# Smart_LIghts.net
KiCad netlist of a schematic drawn in EAGLE
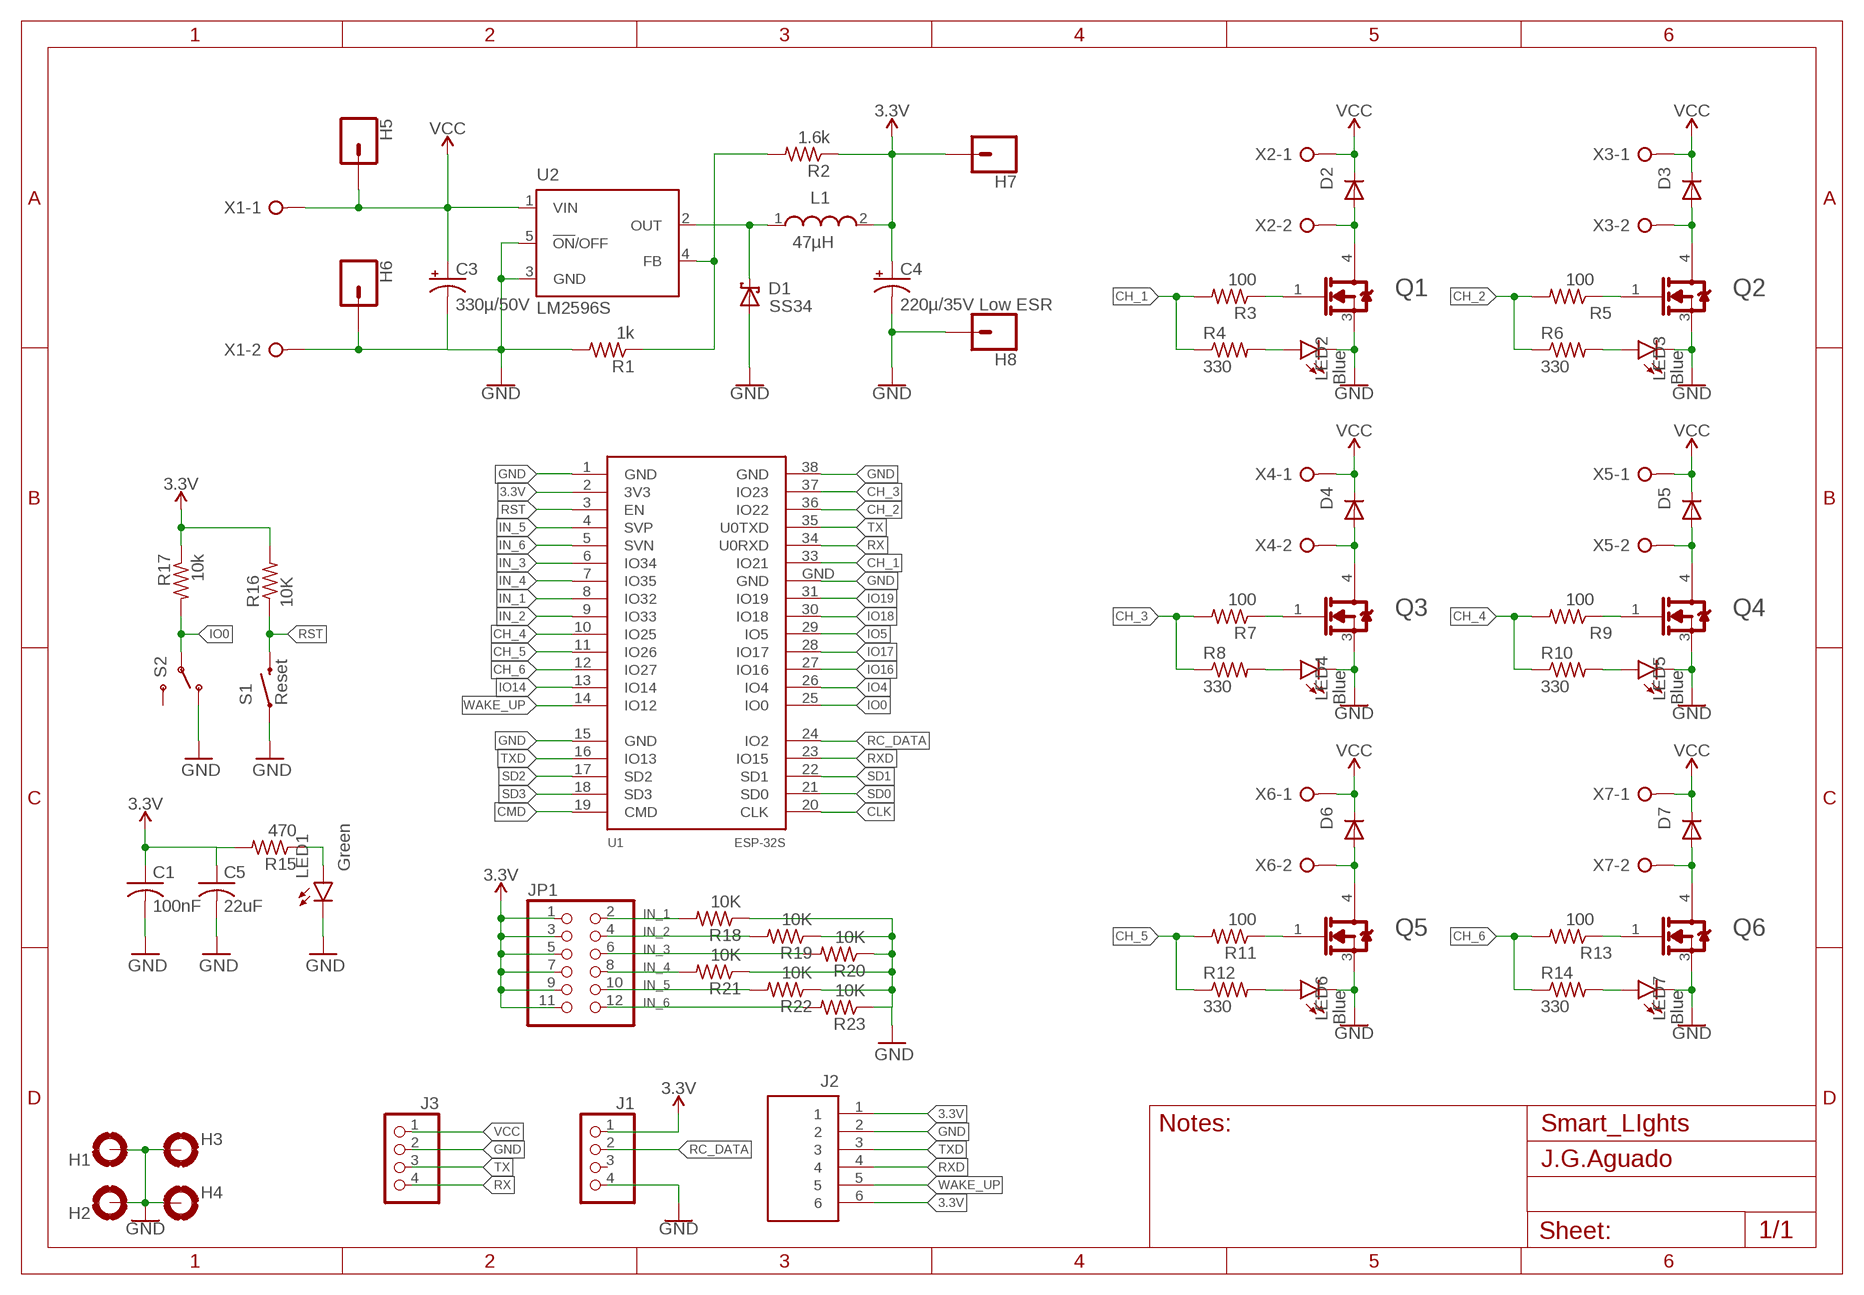
[diagram p0: schematic, sheet 1]

(export (version "E")
  (design (tool "Eeschema 10.0.6"))
  (components
    (comp (ref "C1")
      (value "100nF")
      (footprint "eagle-import:C0603")
      (libsource (lib "eagle-import") (part "C-USC0603"))
    )
    (comp (ref "C3")
      (value "330µ/50V")
      (footprint "eagle-import:PANASONIC_F")
      (fields (field (name "MF") "Panasonic"))
      (libsource (lib "eagle-import") (part "CPOL-USF"))
    )
    (comp (ref "C4")
      (value "220µ/35V Low ESR")
      (footprint "eagle-import:PANASONIC_F")
      (fields (field (name "MF") "Panasonic"))
      (libsource (lib "eagle-import") (part "CPOL-USF"))
    )
    (comp (ref "C5")
      (value "22uF")
      (footprint "eagle-import:C0603")
      (libsource (lib "eagle-import") (part "C-USC0603"))
    )
    (comp (ref "D1")
      (value "SS34")
      (footprint "eagle-import:SMB")
      (libsource (lib "eagle-import") (part "SCHOTTKY-DIODESMD"))
    )
    (comp (ref "D2")
      (value "DIODE-SOD123")
      (footprint "eagle-import:SOD123")
      (libsource (lib "eagle-import") (part "DIODE-SOD123"))
    )
    (comp (ref "D3")
      (value "DIODE-SOD123")
      (footprint "eagle-import:SOD123")
      (libsource (lib "eagle-import") (part "DIODE-SOD123"))
    )
    (comp (ref "D4")
      (value "DIODE-SOD123")
      (footprint "eagle-import:SOD123")
      (libsource (lib "eagle-import") (part "DIODE-SOD123"))
    )
    (comp (ref "D5")
      (value "DIODE-SOD123")
      (footprint "eagle-import:SOD123")
      (libsource (lib "eagle-import") (part "DIODE-SOD123"))
    )
    (comp (ref "D6")
      (value "DIODE-SOD123")
      (footprint "eagle-import:SOD123")
      (libsource (lib "eagle-import") (part "DIODE-SOD123"))
    )
    (comp (ref "D7")
      (value "DIODE-SOD123")
      (footprint "eagle-import:SOD123")
      (libsource (lib "eagle-import") (part "DIODE-SOD123"))
    )
    (comp (ref "H1")
      (value "MOUNT-PAD-ROUND3.0")
      (footprint "eagle-import:3,0-PAD")
      (libsource (lib "eagle-import") (part "MOUNT-PAD-ROUND3.0"))
    )
    (comp (ref "H2")
      (value "MOUNT-PAD-ROUND3.0")
      (footprint "eagle-import:3,0-PAD")
      (libsource (lib "eagle-import") (part "MOUNT-PAD-ROUND3.0"))
    )
    (comp (ref "H3")
      (value "MOUNT-PAD-ROUND3.0")
      (footprint "eagle-import:3,0-PAD")
      (libsource (lib "eagle-import") (part "MOUNT-PAD-ROUND3.0"))
    )
    (comp (ref "H4")
      (value "MOUNT-PAD-ROUND3.0")
      (footprint "eagle-import:3,0-PAD")
      (libsource (lib "eagle-import") (part "MOUNT-PAD-ROUND3.0"))
    )
    (comp (ref "H5")
      (value "CONN_01PTH_2MM")
      (footprint "eagle-import:1X01_2MM")
      (libsource (lib "eagle-import") (part "CONN_01PTH_2MM"))
    )
    (comp (ref "H6")
      (value "CONN_01PTH_2MM")
      (footprint "eagle-import:1X01_2MM")
      (libsource (lib "eagle-import") (part "CONN_01PTH_2MM"))
    )
    (comp (ref "H7")
      (value "CONN_01PTH_2MM")
      (footprint "eagle-import:1X01_2MM")
      (libsource (lib "eagle-import") (part "CONN_01PTH_2MM"))
    )
    (comp (ref "H8")
      (value "CONN_01PTH_2MM")
      (footprint "eagle-import:1X01_2MM")
      (libsource (lib "eagle-import") (part "CONN_01PTH_2MM"))
    )
    (comp (ref "J1")
      (value "PINHD-1X4")
      (footprint "eagle-import:1X04")
      (libsource (lib "eagle-import") (part "PINHD-1X4"))
    )
    (comp (ref "J2")
      (value "JST_6_PIN_VERTICAL")
      (footprint "eagle-import:JST-6-SMD-VERT-1.0MM")
      (libsource (lib "eagle-import") (part "JST_6_PIN_VERTICAL"))
    )
    (comp (ref "J3")
      (value "PINHD-1X4")
      (footprint "eagle-import:1X04")
      (libsource (lib "eagle-import") (part "PINHD-1X4"))
    )
    (comp (ref "JP1")
      (value "PINHD-2X6")
      (footprint "eagle-import:2X06")
      (libsource (lib "eagle-import") (part "PINHD-2X6"))
    )
    (comp (ref "L1")
      (value "47µH")
      (footprint "eagle-import:WE-PD_1260_1245_1280_1210")
      (fields (field (name "MF") "Wuerth"))
      (libsource (lib "eagle-import") (part "WE-PD_1260/1245/1280/1210"))
    )
    (comp (ref "LED1")
      (value "Green")
      (footprint "eagle-import:SML0603")
      (libsource (lib "eagle-import") (part "LEDSML0603"))
    )
    (comp (ref "LED2")
      (value "Blue")
      (footprint "eagle-import:SML0603")
      (libsource (lib "eagle-import") (part "LEDSML0603"))
    )
    (comp (ref "LED3")
      (value "Blue")
      (footprint "eagle-import:SML0603")
      (libsource (lib "eagle-import") (part "LEDSML0603"))
    )
    (comp (ref "LED4")
      (value "Blue")
      (footprint "eagle-import:SML0603")
      (libsource (lib "eagle-import") (part "LEDSML0603"))
    )
    (comp (ref "LED5")
      (value "Blue")
      (footprint "eagle-import:SML0603")
      (libsource (lib "eagle-import") (part "LEDSML0603"))
    )
    (comp (ref "LED6")
      (value "Blue")
      (footprint "eagle-import:SML0603")
      (libsource (lib "eagle-import") (part "LEDSML0603"))
    )
    (comp (ref "LED7")
      (value "Blue")
      (footprint "eagle-import:SML0603")
      (libsource (lib "eagle-import") (part "LEDSML0603"))
    )
    (comp (ref "Q1")
      (value "IRLR2905TRPBF")
      (footprint "eagle-import:INFINEON_TECHNOLOGIES_IRLR2905TRPBF_0")
      (fields
        (field (name "DIGIKEY_PART_NUMBER") "IRLR2905PBFCT-ND")
        (field (name "MF") "Infineon Technologies")
        (field (name "MOUSER_PART_NUMBER") "942-IRLR2905TRPBF")
      )
      (libsource (lib "eagle-import") (part "INFINEON_TECHNOLOGIES_IRLR2905TRPBFINFINEON_TECHNOLOGIES_IRLR2905TRPBF_0_0"))
    )
    (comp (ref "Q2")
      (value "IRLR2905TRPBF")
      (footprint "eagle-import:INFINEON_TECHNOLOGIES_IRLR2905TRPBF_0")
      (fields
        (field (name "DIGIKEY_PART_NUMBER") "IRLR2905PBFCT-ND")
        (field (name "MF") "Infineon Technologies")
        (field (name "MOUSER_PART_NUMBER") "942-IRLR2905TRPBF")
      )
      (libsource (lib "eagle-import") (part "INFINEON_TECHNOLOGIES_IRLR2905TRPBFINFINEON_TECHNOLOGIES_IRLR2905TRPBF_0_0"))
    )
    (comp (ref "Q3")
      (value "IRLR2905TRPBF")
      (footprint "eagle-import:INFINEON_TECHNOLOGIES_IRLR2905TRPBF_0")
      (fields
        (field (name "DIGIKEY_PART_NUMBER") "IRLR2905PBFCT-ND")
        (field (name "MF") "Infineon Technologies")
        (field (name "MOUSER_PART_NUMBER") "942-IRLR2905TRPBF")
      )
      (libsource (lib "eagle-import") (part "INFINEON_TECHNOLOGIES_IRLR2905TRPBFINFINEON_TECHNOLOGIES_IRLR2905TRPBF_0_0"))
    )
    (comp (ref "Q4")
      (value "IRLR2905TRPBF")
      (footprint "eagle-import:INFINEON_TECHNOLOGIES_IRLR2905TRPBF_0")
      (fields
        (field (name "DIGIKEY_PART_NUMBER") "IRLR2905PBFCT-ND")
        (field (name "MF") "Infineon Technologies")
        (field (name "MOUSER_PART_NUMBER") "942-IRLR2905TRPBF")
      )
      (libsource (lib "eagle-import") (part "INFINEON_TECHNOLOGIES_IRLR2905TRPBFINFINEON_TECHNOLOGIES_IRLR2905TRPBF_0_0"))
    )
    (comp (ref "Q5")
      (value "IRLR2905TRPBF")
      (footprint "eagle-import:INFINEON_TECHNOLOGIES_IRLR2905TRPBF_0")
      (fields
        (field (name "DIGIKEY_PART_NUMBER") "IRLR2905PBFCT-ND")
        (field (name "MF") "Infineon Technologies")
        (field (name "MOUSER_PART_NUMBER") "942-IRLR2905TRPBF")
      )
      (libsource (lib "eagle-import") (part "INFINEON_TECHNOLOGIES_IRLR2905TRPBFINFINEON_TECHNOLOGIES_IRLR2905TRPBF_0_0"))
    )
    (comp (ref "Q6")
      (value "IRLR2905TRPBF")
      (footprint "eagle-import:INFINEON_TECHNOLOGIES_IRLR2905TRPBF_0")
      (fields
        (field (name "DIGIKEY_PART_NUMBER") "IRLR2905PBFCT-ND")
        (field (name "MF") "Infineon Technologies")
        (field (name "MOUSER_PART_NUMBER") "942-IRLR2905TRPBF")
      )
      (libsource (lib "eagle-import") (part "INFINEON_TECHNOLOGIES_IRLR2905TRPBFINFINEON_TECHNOLOGIES_IRLR2905TRPBF_0_0"))
    )
    (comp (ref "R1")
      (value "1k")
      (footprint "eagle-import:R0603")
      (libsource (lib "eagle-import") (part "R-US_R0603"))
    )
    (comp (ref "R2")
      (value "1.6k")
      (footprint "eagle-import:R0603")
      (libsource (lib "eagle-import") (part "R-US_R0603"))
    )
    (comp (ref "R3")
      (value "100")
      (footprint "eagle-import:R0603")
      (libsource (lib "eagle-import") (part "R-US_R0603"))
    )
    (comp (ref "R4")
      (value "330")
      (footprint "eagle-import:R0603")
      (libsource (lib "eagle-import") (part "R-US_R0603"))
    )
    (comp (ref "R5")
      (value "100")
      (footprint "eagle-import:R0603")
      (libsource (lib "eagle-import") (part "R-US_R0603"))
    )
    (comp (ref "R6")
      (value "330")
      (footprint "eagle-import:R0603")
      (libsource (lib "eagle-import") (part "R-US_R0603"))
    )
    (comp (ref "R7")
      (value "100")
      (footprint "eagle-import:R0603")
      (libsource (lib "eagle-import") (part "R-US_R0603"))
    )
    (comp (ref "R8")
      (value "330")
      (footprint "eagle-import:R0603")
      (libsource (lib "eagle-import") (part "R-US_R0603"))
    )
    (comp (ref "R9")
      (value "100")
      (footprint "eagle-import:R0603")
      (libsource (lib "eagle-import") (part "R-US_R0603"))
    )
    (comp (ref "R10")
      (value "330")
      (footprint "eagle-import:R0603")
      (libsource (lib "eagle-import") (part "R-US_R0603"))
    )
    (comp (ref "R11")
      (value "100")
      (footprint "eagle-import:R0603")
      (libsource (lib "eagle-import") (part "R-US_R0603"))
    )
    (comp (ref "R12")
      (value "330")
      (footprint "eagle-import:R0603")
      (libsource (lib "eagle-import") (part "R-US_R0603"))
    )
    (comp (ref "R13")
      (value "100")
      (footprint "eagle-import:R0603")
      (libsource (lib "eagle-import") (part "R-US_R0603"))
    )
    (comp (ref "R14")
      (value "330")
      (footprint "eagle-import:R0603")
      (libsource (lib "eagle-import") (part "R-US_R0603"))
    )
    (comp (ref "R15")
      (value "470")
      (footprint "eagle-import:R0603")
      (libsource (lib "eagle-import") (part "R-US_R0603"))
    )
    (comp (ref "R16")
      (value "10K")
      (footprint "eagle-import:R0603")
      (libsource (lib "eagle-import") (part "R-US_R0603"))
    )
    (comp (ref "R17")
      (value "10k")
      (footprint "eagle-import:R0603")
      (libsource (lib "eagle-import") (part "R-US_R0603"))
    )
    (comp (ref "R18")
      (value "10K")
      (footprint "eagle-import:R0603")
      (libsource (lib "eagle-import") (part "R-US_R0603"))
    )
    (comp (ref "R19")
      (value "10K")
      (footprint "eagle-import:R0603")
      (libsource (lib "eagle-import") (part "R-US_R0603"))
    )
    (comp (ref "R20")
      (value "10K")
      (footprint "eagle-import:R0603")
      (libsource (lib "eagle-import") (part "R-US_R0603"))
    )
    (comp (ref "R21")
      (value "10K")
      (footprint "eagle-import:R0603")
      (libsource (lib "eagle-import") (part "R-US_R0603"))
    )
    (comp (ref "R22")
      (value "10K")
      (footprint "eagle-import:R0603")
      (libsource (lib "eagle-import") (part "R-US_R0603"))
    )
    (comp (ref "R23")
      (value "10K")
      (footprint "eagle-import:R0603")
      (libsource (lib "eagle-import") (part "R-US_R0603"))
    )
    (comp (ref "S1")
      (value "Reset")
      (footprint "eagle-import:TACTILE_SWITCH_TALL")
      (libsource (lib "eagle-import") (part "SWITCH-MOMENTARY-2SMD-4"))
    )
    (comp (ref "S2")
      (value "SWITCH_SPDT")
      (footprint "eagle-import:KPS-1290")
      (libsource (lib "eagle-import") (part "SWITCH_SPDT"))
    )
    (comp (ref "U1")
      (value "ESP-32S")
      (footprint "eagle-import:ESP-32S")
      (libsource (lib "eagle-import") (part "ESP-32S"))
    )
    (comp (ref "U2")
      (value "LM2596S")
      (footprint "eagle-import:TO263-5")
      (fields (field (name "MF") "NATIONAL SEMICONDUCTOR") (field (name "MPN") "LM2596S-ADJ/NOPB"))
      (libsource (lib "eagle-import") (part "LM2596S"))
    )
    (comp (ref "X1")
      (value "W237-02P")
      (footprint "eagle-import:W237-132")
      (libsource (lib "eagle-import") (part "W237-02P"))
    )
    (comp (ref "X2")
      (value "W237-02P")
      (footprint "eagle-import:W237-132")
      (libsource (lib "eagle-import") (part "W237-02P"))
    )
    (comp (ref "X3")
      (value "W237-02P")
      (footprint "eagle-import:W237-132")
      (libsource (lib "eagle-import") (part "W237-02P"))
    )
    (comp (ref "X4")
      (value "W237-02P")
      (footprint "eagle-import:W237-132")
      (libsource (lib "eagle-import") (part "W237-02P"))
    )
    (comp (ref "X5")
      (value "W237-02P")
      (footprint "eagle-import:W237-132")
      (libsource (lib "eagle-import") (part "W237-02P"))
    )
    (comp (ref "X6")
      (value "W237-02P")
      (footprint "eagle-import:W237-132")
      (libsource (lib "eagle-import") (part "W237-02P"))
    )
    (comp (ref "X7")
      (value "W237-02P")
      (footprint "eagle-import:W237-132")
      (libsource (lib "eagle-import") (part "W237-02P"))
    )
  )
  (nets
    (net (code "1") (name "3.3V") (class "Default")
      (node (ref "C1") (pin "1") (pinfunction "1_1") (pintype "passive"))
      (node (ref "C4") (pin "+") (pinfunction "+_+") (pintype "passive"))
      (node (ref "C5") (pin "1") (pinfunction "1_1") (pintype "passive"))
      (node (ref "H7") (pin "1") (pinfunction "1_1") (pintype "passive"))
      (node (ref "J1") (pin "1") (pinfunction "1_1") (pintype "passive"))
      (node (ref "J2") (pin "1") (pinfunction "1_1") (pintype "bidirectional"))
      (node (ref "J2") (pin "6") (pinfunction "6_6") (pintype "bidirectional"))
      (node (ref "JP1") (pin "1") (pinfunction "1_1") (pintype "passive"))
      (node (ref "JP1") (pin "11") (pinfunction "11_11") (pintype "passive"))
      (node (ref "JP1") (pin "3") (pinfunction "3_3") (pintype "passive"))
      (node (ref "JP1") (pin "5") (pinfunction "5_5") (pintype "passive"))
      (node (ref "JP1") (pin "7") (pinfunction "7_7") (pintype "passive"))
      (node (ref "JP1") (pin "9") (pinfunction "9_9") (pintype "passive"))
      (node (ref "L1") (pin "2") (pinfunction "2_2") (pintype "passive"))
      (node (ref "R15") (pin "2") (pinfunction "2_2") (pintype "passive"))
      (node (ref "R16") (pin "2") (pinfunction "2_2") (pintype "passive"))
      (node (ref "R17") (pin "1") (pinfunction "1_1") (pintype "passive"))
      (node (ref "R2") (pin "1") (pinfunction "1_1") (pintype "passive"))
      (node (ref "U1") (pin "2") (pinfunction "3V3_2") (pintype "power_in"))
    )
    (net (code "2") (name "CH_1") (class "Default")
      (node (ref "R3") (pin "2") (pinfunction "2_2") (pintype "passive"))
      (node (ref "R4") (pin "1") (pinfunction "1_1") (pintype "passive"))
      (node (ref "U1") (pin "33") (pinfunction "IO21_33") (pintype "bidirectional"))
    )
    (net (code "3") (name "CH_2") (class "Default")
      (node (ref "R5") (pin "2") (pinfunction "2_2") (pintype "passive"))
      (node (ref "R6") (pin "1") (pinfunction "1_1") (pintype "passive"))
      (node (ref "U1") (pin "36") (pinfunction "IO22_36") (pintype "bidirectional"))
    )
    (net (code "4") (name "CH_3") (class "Default")
      (node (ref "R7") (pin "2") (pinfunction "2_2") (pintype "passive"))
      (node (ref "R8") (pin "1") (pinfunction "1_1") (pintype "passive"))
      (node (ref "U1") (pin "37") (pinfunction "IO23_37") (pintype "bidirectional"))
    )
    (net (code "5") (name "CH_4") (class "Default")
      (node (ref "R10") (pin "1") (pinfunction "1_1") (pintype "passive"))
      (node (ref "R9") (pin "2") (pinfunction "2_2") (pintype "passive"))
      (node (ref "U1") (pin "10") (pinfunction "IO25_10") (pintype "bidirectional"))
    )
    (net (code "6") (name "CH_5") (class "Default")
      (node (ref "R11") (pin "2") (pinfunction "2_2") (pintype "passive"))
      (node (ref "R12") (pin "1") (pinfunction "1_1") (pintype "passive"))
      (node (ref "U1") (pin "11") (pinfunction "IO26_11") (pintype "bidirectional"))
    )
    (net (code "7") (name "CH_6") (class "Default")
      (node (ref "R13") (pin "2") (pinfunction "2_2") (pintype "passive"))
      (node (ref "R14") (pin "1") (pinfunction "1_1") (pintype "passive"))
      (node (ref "U1") (pin "12") (pinfunction "IO27_12") (pintype "bidirectional"))
    )
    (net (code "8") (name "CLK") (class "Default")
      (node (ref "U1") (pin "20") (pinfunction "CLK_20") (pintype "bidirectional"))
    )
    (net (code "9") (name "CMD") (class "Default")
      (node (ref "U1") (pin "19") (pinfunction "CMD_19") (pintype "bidirectional"))
    )
    (net (code "10") (name "GND") (class "Default")
      (node (ref "C1") (pin "2") (pinfunction "2_2") (pintype "passive"))
      (node (ref "C3") (pin "-") (pinfunction "-_-") (pintype "passive"))
      (node (ref "C4") (pin "-") (pinfunction "-_-") (pintype "passive"))
      (node (ref "C5") (pin "2") (pinfunction "2_2") (pintype "passive"))
      (node (ref "D1") (pin "A") (pinfunction "A_A") (pintype "passive"))
      (node (ref "H1") (pin "B3,0") (pinfunction "MOUNT_B3,0") (pintype "passive"))
      (node (ref "H2") (pin "B3,0") (pinfunction "MOUNT_B3,0") (pintype "passive"))
      (node (ref "H3") (pin "B3,0") (pinfunction "MOUNT_B3,0") (pintype "passive"))
      (node (ref "H4") (pin "B3,0") (pinfunction "MOUNT_B3,0") (pintype "passive"))
      (node (ref "H6") (pin "1") (pinfunction "1_1") (pintype "passive"))
      (node (ref "H8") (pin "1") (pinfunction "1_1") (pintype "passive"))
      (node (ref "J1") (pin "4") (pinfunction "4_4") (pintype "passive"))
      (node (ref "J2") (pin "2") (pinfunction "2_2") (pintype "bidirectional"))
      (node (ref "J3") (pin "2") (pinfunction "2_2") (pintype "passive"))
      (node (ref "LED1") (pin "C") (pinfunction "C_C") (pintype "passive"))
      (node (ref "LED2") (pin "C") (pinfunction "C_C") (pintype "passive"))
      (node (ref "LED3") (pin "C") (pinfunction "C_C") (pintype "passive"))
      (node (ref "LED4") (pin "C") (pinfunction "C_C") (pintype "passive"))
      (node (ref "LED5") (pin "C") (pinfunction "C_C") (pintype "passive"))
      (node (ref "LED6") (pin "C") (pinfunction "C_C") (pintype "passive"))
      (node (ref "LED7") (pin "C") (pinfunction "C_C") (pintype "passive"))
      (node (ref "Q1") (pin "3") (pinfunction "SOURCE_3") (pintype "passive"))
      (node (ref "Q2") (pin "3") (pinfunction "SOURCE_3") (pintype "passive"))
      (node (ref "Q3") (pin "3") (pinfunction "SOURCE_3") (pintype "passive"))
      (node (ref "Q4") (pin "3") (pinfunction "SOURCE_3") (pintype "passive"))
      (node (ref "Q5") (pin "3") (pinfunction "SOURCE_3") (pintype "passive"))
      (node (ref "Q6") (pin "3") (pinfunction "SOURCE_3") (pintype "passive"))
      (node (ref "R1") (pin "2") (pinfunction "2_2") (pintype "passive"))
      (node (ref "R18") (pin "1") (pinfunction "1_1") (pintype "passive"))
      (node (ref "R19") (pin "1") (pinfunction "1_1") (pintype "passive"))
      (node (ref "R20") (pin "1") (pinfunction "1_1") (pintype "passive"))
      (node (ref "R21") (pin "1") (pinfunction "1_1") (pintype "passive"))
      (node (ref "R22") (pin "1") (pinfunction "1_1") (pintype "passive"))
      (node (ref "R23") (pin "1") (pinfunction "1_1") (pintype "passive"))
      (node (ref "S1") (pin "A2") (pinfunction "1_A2") (pintype "passive"))
      (node (ref "S2") (pin "O") (pinfunction "O_O") (pintype "passive"))
      (node (ref "U1") (pin "1") (pinfunction "GND_1") (pintype "power_in"))
      (node (ref "U1") (pin "15") (pinfunction "GND_15") (pintype "power_in"))
      (node (ref "U1") (pin "38") (pinfunction "GND_38") (pintype "power_in"))
      (node (ref "U1") (pin "GND") (pinfunction "GND_GND") (pintype "power_in"))
      (node (ref "U2") (pin "3") (pinfunction "GND_3") (pintype "power_in"))
      (node (ref "U2") (pin "5") (pinfunction "~{ON}/OFF_5") (pintype "input"))
      (node (ref "X1") (pin "2") (pinfunction "KL_2") (pintype "passive"))
    )
    (net (code "11") (name "IN_1") (class "Default")
      (node (ref "JP1") (pin "2") (pinfunction "2_2") (pintype "passive"))
      (node (ref "R18") (pin "2") (pinfunction "2_2") (pintype "passive"))
      (node (ref "U1") (pin "8") (pinfunction "IO32_8") (pintype "bidirectional"))
    )
    (net (code "12") (name "IN_2") (class "Default")
      (node (ref "JP1") (pin "4") (pinfunction "4_4") (pintype "passive"))
      (node (ref "R19") (pin "2") (pinfunction "2_2") (pintype "passive"))
      (node (ref "U1") (pin "9") (pinfunction "IO33_9") (pintype "bidirectional"))
    )
    (net (code "13") (name "IN_3") (class "Default")
      (node (ref "JP1") (pin "6") (pinfunction "6_6") (pintype "passive"))
      (node (ref "R20") (pin "2") (pinfunction "2_2") (pintype "passive"))
      (node (ref "U1") (pin "6") (pinfunction "IO34_6") (pintype "bidirectional"))
    )
    (net (code "14") (name "IN_4") (class "Default")
      (node (ref "JP1") (pin "8") (pinfunction "8_8") (pintype "passive"))
      (node (ref "R21") (pin "2") (pinfunction "2_2") (pintype "passive"))
      (node (ref "U1") (pin "7") (pinfunction "IO35_7") (pintype "bidirectional"))
    )
    (net (code "15") (name "IN_5") (class "Default")
      (node (ref "JP1") (pin "10") (pinfunction "10_10") (pintype "passive"))
      (node (ref "R22") (pin "2") (pinfunction "2_2") (pintype "passive"))
      (node (ref "U1") (pin "4") (pinfunction "SVP_4") (pintype "bidirectional"))
    )
    (net (code "16") (name "IN_6") (class "Default")
      (node (ref "JP1") (pin "12") (pinfunction "12_12") (pintype "passive"))
      (node (ref "R23") (pin "2") (pinfunction "2_2") (pintype "passive"))
      (node (ref "U1") (pin "5") (pinfunction "SVN_5") (pintype "bidirectional"))
    )
    (net (code "17") (name "IO0") (class "Default")
      (node (ref "R17") (pin "2") (pinfunction "2_2") (pintype "passive"))
      (node (ref "S2") (pin "P") (pinfunction "P_P") (pintype "passive"))
      (node (ref "U1") (pin "25") (pinfunction "IO0_25") (pintype "bidirectional"))
    )
    (net (code "18") (name "IO4") (class "Default")
      (node (ref "U1") (pin "26") (pinfunction "IO4_26") (pintype "bidirectional"))
    )
    (net (code "19") (name "IO5") (class "Default")
      (node (ref "U1") (pin "29") (pinfunction "IO5_29") (pintype "bidirectional"))
    )
    (net (code "20") (name "IO14") (class "Default")
      (node (ref "U1") (pin "13") (pinfunction "IO14_13") (pintype "bidirectional"))
    )
    (net (code "21") (name "IO16") (class "Default")
      (node (ref "U1") (pin "27") (pinfunction "IO16_27") (pintype "bidirectional"))
    )
    (net (code "22") (name "IO17") (class "Default")
      (node (ref "U1") (pin "28") (pinfunction "IO17_28") (pintype "bidirectional"))
    )
    (net (code "23") (name "IO18") (class "Default")
      (node (ref "U1") (pin "30") (pinfunction "IO18_30") (pintype "bidirectional"))
    )
    (net (code "24") (name "IO19") (class "Default")
      (node (ref "U1") (pin "31") (pinfunction "IO19_31") (pintype "bidirectional"))
    )
    (net (code "25") (name "Net-(LED1-PadA)") (class "Default")
      (node (ref "LED1") (pin "A") (pinfunction "A_A") (pintype "passive"))
      (node (ref "R15") (pin "1") (pinfunction "1_1") (pintype "passive"))
    )
    (net (code "26") (name "Net-(LED2-PadA)") (class "Default")
      (node (ref "LED2") (pin "A") (pinfunction "A_A") (pintype "passive"))
      (node (ref "R4") (pin "2") (pinfunction "2_2") (pintype "passive"))
    )
    (net (code "27") (name "Net-(LED3-PadA)") (class "Default")
      (node (ref "LED3") (pin "A") (pinfunction "A_A") (pintype "passive"))
      (node (ref "R6") (pin "2") (pinfunction "2_2") (pintype "passive"))
    )
    (net (code "28") (name "Net-(LED4-PadA)") (class "Default")
      (node (ref "LED4") (pin "A") (pinfunction "A_A") (pintype "passive"))
      (node (ref "R8") (pin "2") (pinfunction "2_2") (pintype "passive"))
    )
    (net (code "29") (name "Net-(LED5-PadA)") (class "Default")
      (node (ref "LED5") (pin "A") (pinfunction "A_A") (pintype "passive"))
      (node (ref "R10") (pin "2") (pinfunction "2_2") (pintype "passive"))
    )
    (net (code "30") (name "Net-(LED6-PadA)") (class "Default")
      (node (ref "LED6") (pin "A") (pinfunction "A_A") (pintype "passive"))
      (node (ref "R12") (pin "2") (pinfunction "2_2") (pintype "passive"))
    )
    (net (code "31") (name "Net-(LED7-PadA)") (class "Default")
      (node (ref "LED7") (pin "A") (pinfunction "A_A") (pintype "passive"))
      (node (ref "R14") (pin "2") (pinfunction "2_2") (pintype "passive"))
    )
    (net (code "32") (name "Net-(Q1-DRAIN)") (class "Default")
      (node (ref "D2") (pin "A") (pinfunction "A_A") (pintype "passive"))
      (node (ref "Q1") (pin "4") (pinfunction "DRAIN_4") (pintype "passive"))
      (node (ref "X2") (pin "2") (pinfunction "KL_2") (pintype "passive"))
    )
    (net (code "33") (name "Net-(Q1-GATE)") (class "Default")
      (node (ref "Q1") (pin "1") (pinfunction "GATE_1") (pintype "passive"))
      (node (ref "R3") (pin "1") (pinfunction "1_1") (pintype "passive"))
    )
    (net (code "34") (name "Net-(Q2-DRAIN)") (class "Default")
      (node (ref "D3") (pin "A") (pinfunction "A_A") (pintype "passive"))
      (node (ref "Q2") (pin "4") (pinfunction "DRAIN_4") (pintype "passive"))
      (node (ref "X3") (pin "2") (pinfunction "KL_2") (pintype "passive"))
    )
    (net (code "35") (name "Net-(Q2-GATE)") (class "Default")
      (node (ref "Q2") (pin "1") (pinfunction "GATE_1") (pintype "passive"))
      (node (ref "R5") (pin "1") (pinfunction "1_1") (pintype "passive"))
    )
    (net (code "36") (name "Net-(Q3-DRAIN)") (class "Default")
      (node (ref "D4") (pin "A") (pinfunction "A_A") (pintype "passive"))
      (node (ref "Q3") (pin "4") (pinfunction "DRAIN_4") (pintype "passive"))
      (node (ref "X4") (pin "2") (pinfunction "KL_2") (pintype "passive"))
    )
    (net (code "37") (name "Net-(Q3-GATE)") (class "Default")
      (node (ref "Q3") (pin "1") (pinfunction "GATE_1") (pintype "passive"))
      (node (ref "R7") (pin "1") (pinfunction "1_1") (pintype "passive"))
    )
    (net (code "38") (name "Net-(Q4-DRAIN)") (class "Default")
      (node (ref "D5") (pin "A") (pinfunction "A_A") (pintype "passive"))
      (node (ref "Q4") (pin "4") (pinfunction "DRAIN_4") (pintype "passive"))
      (node (ref "X5") (pin "2") (pinfunction "KL_2") (pintype "passive"))
    )
    (net (code "39") (name "Net-(Q4-GATE)") (class "Default")
      (node (ref "Q4") (pin "1") (pinfunction "GATE_1") (pintype "passive"))
      (node (ref "R9") (pin "1") (pinfunction "1_1") (pintype "passive"))
    )
    (net (code "40") (name "Net-(Q5-DRAIN)") (class "Default")
      (node (ref "D6") (pin "A") (pinfunction "A_A") (pintype "passive"))
      (node (ref "Q5") (pin "4") (pinfunction "DRAIN_4") (pintype "passive"))
      (node (ref "X6") (pin "2") (pinfunction "KL_2") (pintype "passive"))
    )
    (net (code "41") (name "Net-(Q5-GATE)") (class "Default")
      (node (ref "Q5") (pin "1") (pinfunction "GATE_1") (pintype "passive"))
      (node (ref "R11") (pin "1") (pinfunction "1_1") (pintype "passive"))
    )
    (net (code "42") (name "Net-(Q6-DRAIN)") (class "Default")
      (node (ref "D7") (pin "A") (pinfunction "A_A") (pintype "passive"))
      (node (ref "Q6") (pin "4") (pinfunction "DRAIN_4") (pintype "passive"))
      (node (ref "X7") (pin "2") (pinfunction "KL_2") (pintype "passive"))
    )
    (net (code "43") (name "Net-(Q6-GATE)") (class "Default")
      (node (ref "Q6") (pin "1") (pinfunction "GATE_1") (pintype "passive"))
      (node (ref "R13") (pin "1") (pinfunction "1_1") (pintype "passive"))
    )
    (net (code "44") (name "Net-(U2-FB)") (class "Default")
      (node (ref "R1") (pin "1") (pinfunction "1_1") (pintype "passive"))
      (node (ref "R2") (pin "2") (pinfunction "2_2") (pintype "passive"))
      (node (ref "U2") (pin "4") (pinfunction "FB_4") (pintype "input"))
    )
    (net (code "45") (name "Net-(U2-OUT)") (class "Default")
      (node (ref "D1") (pin "C") (pinfunction "C_C") (pintype "passive"))
      (node (ref "L1") (pin "1") (pinfunction "1_1") (pintype "passive"))
      (node (ref "U2") (pin "2") (pinfunction "OUT_2") (pintype "output"))
    )
    (net (code "46") (name "RC_DATA") (class "Default")
      (node (ref "J1") (pin "2") (pinfunction "2_2") (pintype "passive"))
      (node (ref "U1") (pin "24") (pinfunction "IO2_24") (pintype "bidirectional"))
    )
    (net (code "47") (name "RST") (class "Default")
      (node (ref "R16") (pin "1") (pinfunction "1_1") (pintype "passive"))
      (node (ref "S1") (pin "B2") (pinfunction "2_B2") (pintype "passive"))
      (node (ref "U1") (pin "3") (pinfunction "EN_3") (pintype "input"))
    )
    (net (code "48") (name "RX") (class "Default")
      (node (ref "J3") (pin "4") (pinfunction "4_4") (pintype "passive"))
      (node (ref "U1") (pin "34") (pinfunction "U0RXD_34") (pintype "bidirectional"))
    )
    (net (code "49") (name "RXD") (class "Default")
      (node (ref "J2") (pin "4") (pinfunction "4_4") (pintype "bidirectional"))
      (node (ref "U1") (pin "23") (pinfunction "IO15_23") (pintype "bidirectional"))
    )
    (net (code "50") (name "SD0") (class "Default")
      (node (ref "U1") (pin "21") (pinfunction "SD0_21") (pintype "bidirectional"))
    )
    (net (code "51") (name "SD1") (class "Default")
      (node (ref "U1") (pin "22") (pinfunction "SD1_22") (pintype "bidirectional"))
    )
    (net (code "52") (name "SD2") (class "Default")
      (node (ref "U1") (pin "17") (pinfunction "SD2_17") (pintype "bidirectional"))
    )
    (net (code "53") (name "SD3") (class "Default")
      (node (ref "U1") (pin "18") (pinfunction "SD3_18") (pintype "bidirectional"))
    )
    (net (code "54") (name "TX") (class "Default")
      (node (ref "J3") (pin "3") (pinfunction "3_3") (pintype "passive"))
      (node (ref "U1") (pin "35") (pinfunction "U0TXD_35") (pintype "bidirectional"))
    )
    (net (code "55") (name "TXD") (class "Default")
      (node (ref "J2") (pin "3") (pinfunction "3_3") (pintype "bidirectional"))
      (node (ref "U1") (pin "16") (pinfunction "IO13_16") (pintype "bidirectional"))
    )
    (net (code "56") (name "VCC") (class "Default")
      (node (ref "C3") (pin "+") (pinfunction "+_+") (pintype "passive"))
      (node (ref "D2") (pin "C") (pinfunction "C_C") (pintype "passive"))
      (node (ref "D3") (pin "C") (pinfunction "C_C") (pintype "passive"))
      (node (ref "D4") (pin "C") (pinfunction "C_C") (pintype "passive"))
      (node (ref "D5") (pin "C") (pinfunction "C_C") (pintype "passive"))
      (node (ref "D6") (pin "C") (pinfunction "C_C") (pintype "passive"))
      (node (ref "D7") (pin "C") (pinfunction "C_C") (pintype "passive"))
      (node (ref "H5") (pin "1") (pinfunction "1_1") (pintype "passive"))
      (node (ref "J3") (pin "1") (pinfunction "1_1") (pintype "passive"))
      (node (ref "U2") (pin "1") (pinfunction "VIN_1") (pintype "input"))
      (node (ref "X1") (pin "1") (pinfunction "KL_1") (pintype "passive"))
      (node (ref "X2") (pin "1") (pinfunction "KL_1") (pintype "passive"))
      (node (ref "X3") (pin "1") (pinfunction "KL_1") (pintype "passive"))
      (node (ref "X4") (pin "1") (pinfunction "KL_1") (pintype "passive"))
      (node (ref "X5") (pin "1") (pinfunction "KL_1") (pintype "passive"))
      (node (ref "X6") (pin "1") (pinfunction "KL_1") (pintype "passive"))
      (node (ref "X7") (pin "1") (pinfunction "KL_1") (pintype "passive"))
    )
    (net (code "57") (name "WAKE_UP") (class "Default")
      (node (ref "J2") (pin "5") (pinfunction "5_5") (pintype "bidirectional"))
      (node (ref "U1") (pin "14") (pinfunction "IO12_14") (pintype "bidirectional"))
    )
    (net (code "58") (name "unconnected-(J1-Pad3)") (class "Default")
      (node (ref "J1") (pin "3") (pinfunction "3_3") (pintype "passive"))
    )
    (net (code "59") (name "unconnected-(S2-PadS)") (class "Default")
      (node (ref "S2") (pin "S") (pinfunction "S_S") (pintype "passive"))
    )
  )
)
